# tm4cShield_eStop_v1_0.net
KiCad netlist of a schematic drawn in EAGLE
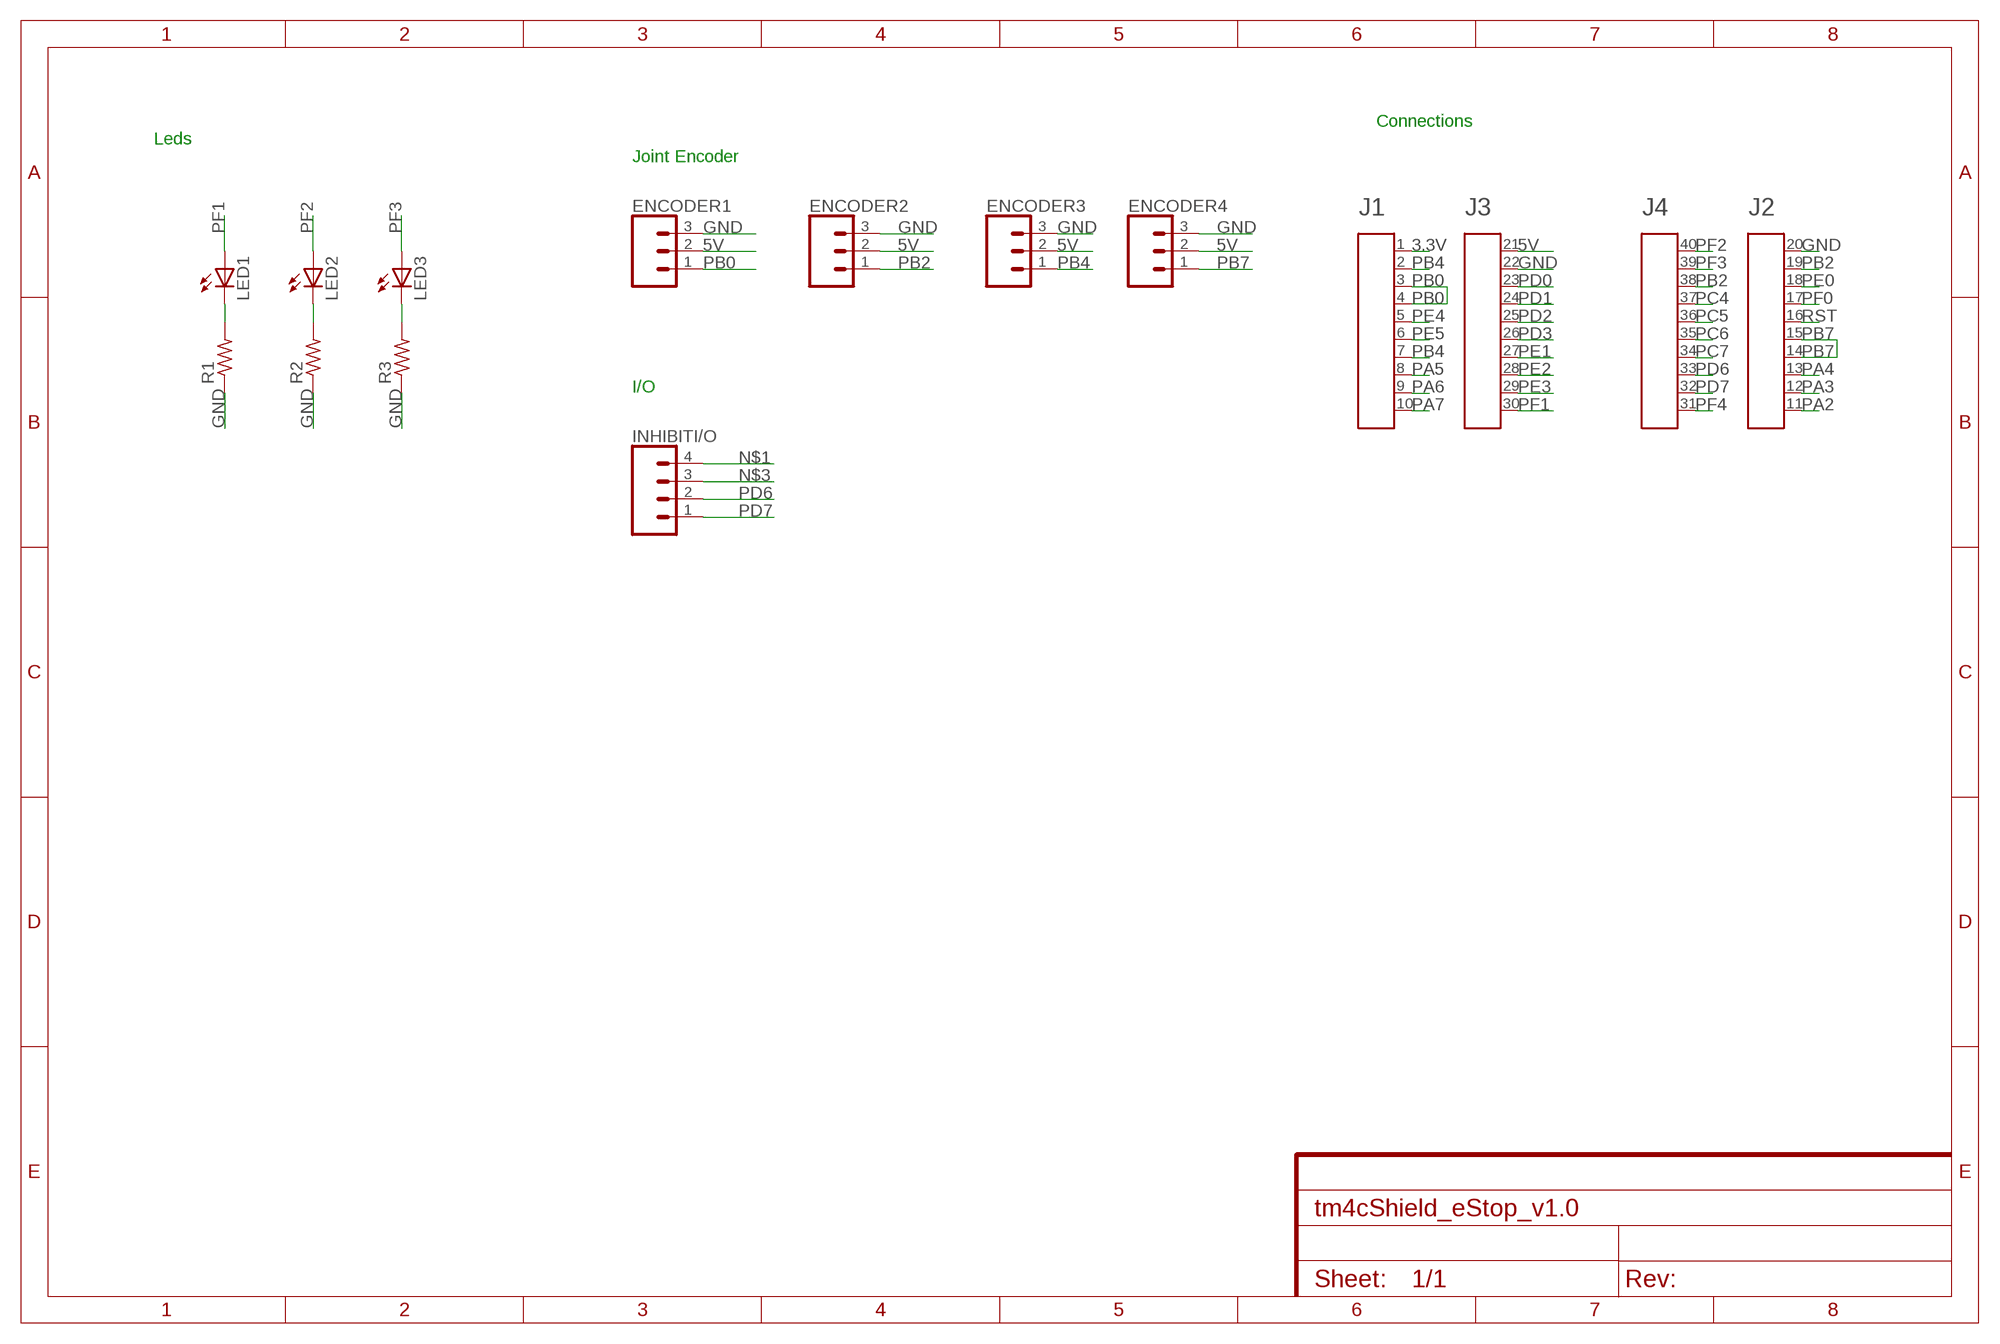
[diagram p0: schematic, sheet 1]

(export (version "E")
  (design (tool "Eeschema 10.0.6"))
  (components
    (comp (ref "A1")
      (value "HEADER4X10-BOOSTERPACK")
      (footprint "eagle-import:4X10-BOOSTERPACK")
      (libsource (lib "eagle-import") (part "HEADER4X10-BOOSTERPACK"))
    )
    (comp (ref "ENCODER1")
      (value "CONN_03JST-PTH-VERT")
      (footprint "eagle-import:JST-3-PTH-VERT")
      (libsource (lib "eagle-import") (part "CONN_03JST-PTH-VERT"))
    )
    (comp (ref "ENCODER2")
      (value "CONN_03JST-PTH-VERT")
      (footprint "eagle-import:JST-3-PTH-VERT")
      (libsource (lib "eagle-import") (part "CONN_03JST-PTH-VERT"))
    )
    (comp (ref "ENCODER3")
      (value "CONN_03JST-PTH-VERT")
      (footprint "eagle-import:JST-3-PTH-VERT")
      (libsource (lib "eagle-import") (part "CONN_03JST-PTH-VERT"))
    )
    (comp (ref "ENCODER4")
      (value "CONN_03JST-PTH-VERT")
      (footprint "eagle-import:JST-3-PTH-VERT")
      (libsource (lib "eagle-import") (part "CONN_03JST-PTH-VERT"))
    )
    (comp (ref "INHIBITI/O")
      (value "CONN_04JST-PTH-VERT")
      (footprint "eagle-import:JST-4-PTH-VERT")
      (libsource (lib "eagle-import") (part "CONN_04JST-PTH-VERT"))
    )
    (comp (ref "LED1")
      (value "LED0603")
      (footprint "eagle-import:LED-0603")
      (libsource (lib "eagle-import") (part "LED0603"))
    )
    (comp (ref "LED2")
      (value "LED0603")
      (footprint "eagle-import:LED-0603")
      (libsource (lib "eagle-import") (part "LED0603"))
    )
    (comp (ref "LED3")
      (value "LED0603")
      (footprint "eagle-import:LED-0603")
      (libsource (lib "eagle-import") (part "LED0603"))
    )
    (comp (ref "R1")
      (value "RESISTOR_0603")
      (footprint "eagle-import:RESC0603")
      (libsource (lib "eagle-import") (part "RESISTOR_0603"))
    )
    (comp (ref "R2")
      (value "RESISTOR_0603")
      (footprint "eagle-import:RESC0603")
      (libsource (lib "eagle-import") (part "RESISTOR_0603"))
    )
    (comp (ref "R3")
      (value "RESISTOR_0603")
      (footprint "eagle-import:RESC0603")
      (libsource (lib "eagle-import") (part "RESISTOR_0603"))
    )
  )
  (nets
    (net (code "1") (name "/3.3V") (class "Default")
      (node (ref "A1") (pin "1") (pinfunction "P$1_1") (pintype "bidirectional"))
    )
    (net (code "2") (name "/5V") (class "Default")
      (node (ref "A1") (pin "21") (pinfunction "P$21_21") (pintype "bidirectional"))
      (node (ref "ENCODER1") (pin "2") (pinfunction "2_2") (pintype "passive"))
      (node (ref "ENCODER2") (pin "2") (pinfunction "2_2") (pintype "passive"))
      (node (ref "ENCODER3") (pin "2") (pinfunction "2_2") (pintype "passive"))
      (node (ref "ENCODER4") (pin "2") (pinfunction "2_2") (pintype "passive"))
    )
    (net (code "3") (name "/GND") (class "Default")
      (node (ref "A1") (pin "20") (pinfunction "P$20_20") (pintype "bidirectional"))
      (node (ref "A1") (pin "22") (pinfunction "P$22_22") (pintype "bidirectional"))
      (node (ref "ENCODER1") (pin "3") (pinfunction "3_3") (pintype "passive"))
      (node (ref "ENCODER2") (pin "3") (pinfunction "3_3") (pintype "passive"))
      (node (ref "ENCODER3") (pin "3") (pinfunction "3_3") (pintype "passive"))
      (node (ref "ENCODER4") (pin "3") (pinfunction "3_3") (pintype "passive"))
      (node (ref "R1") (pin "1") (pinfunction "1_1") (pintype "passive"))
      (node (ref "R2") (pin "1") (pinfunction "1_1") (pintype "passive"))
      (node (ref "R3") (pin "1") (pinfunction "1_1") (pintype "passive"))
    )
    (net (code "4") (name "/N$1") (class "Default")
      (node (ref "INHIBITI/O") (pin "4") (pinfunction "4_4") (pintype "passive"))
    )
    (net (code "5") (name "/N$3") (class "Default")
      (node (ref "INHIBITI/O") (pin "3") (pinfunction "3_3") (pintype "passive"))
    )
    (net (code "6") (name "/PA2") (class "Default")
      (node (ref "A1") (pin "11") (pinfunction "P$11_11") (pintype "bidirectional"))
    )
    (net (code "7") (name "/PA3") (class "Default")
      (node (ref "A1") (pin "12") (pinfunction "P$12_12") (pintype "bidirectional"))
    )
    (net (code "8") (name "/PA4") (class "Default")
      (node (ref "A1") (pin "13") (pinfunction "P$13_13") (pintype "bidirectional"))
    )
    (net (code "9") (name "/PA5") (class "Default")
      (node (ref "A1") (pin "8") (pinfunction "P$8_8") (pintype "bidirectional"))
    )
    (net (code "10") (name "/PA6") (class "Default")
      (node (ref "A1") (pin "9") (pinfunction "P$9_9") (pintype "bidirectional"))
    )
    (net (code "11") (name "/PA7") (class "Default")
      (node (ref "A1") (pin "10") (pinfunction "P$10_10") (pintype "bidirectional"))
    )
    (net (code "12") (name "/PB0") (class "Default")
      (node (ref "A1") (pin "3") (pinfunction "P$3_3") (pintype "bidirectional"))
      (node (ref "A1") (pin "4") (pinfunction "P$4_4") (pintype "bidirectional"))
      (node (ref "ENCODER1") (pin "1") (pinfunction "1_1") (pintype "passive"))
    )
    (net (code "13") (name "/PB2") (class "Default")
      (node (ref "A1") (pin "19") (pinfunction "P$19_19") (pintype "bidirectional"))
      (node (ref "A1") (pin "38") (pinfunction "P$38_38") (pintype "bidirectional"))
      (node (ref "ENCODER2") (pin "1") (pinfunction "1_1") (pintype "passive"))
    )
    (net (code "14") (name "/PB4") (class "Default")
      (node (ref "A1") (pin "2") (pinfunction "P$2_2") (pintype "bidirectional"))
      (node (ref "A1") (pin "7") (pinfunction "P$7_7") (pintype "bidirectional"))
      (node (ref "ENCODER3") (pin "1") (pinfunction "1_1") (pintype "passive"))
    )
    (net (code "15") (name "/PB7") (class "Default")
      (node (ref "A1") (pin "14") (pinfunction "P$14_14") (pintype "bidirectional"))
      (node (ref "A1") (pin "15") (pinfunction "P$15_15") (pintype "bidirectional"))
      (node (ref "ENCODER4") (pin "1") (pinfunction "1_1") (pintype "passive"))
    )
    (net (code "16") (name "/PC4") (class "Default")
      (node (ref "A1") (pin "37") (pinfunction "P$37_37") (pintype "bidirectional"))
    )
    (net (code "17") (name "/PC5") (class "Default")
      (node (ref "A1") (pin "36") (pinfunction "P$36_36") (pintype "bidirectional"))
    )
    (net (code "18") (name "/PC6") (class "Default")
      (node (ref "A1") (pin "35") (pinfunction "P$35_35") (pintype "bidirectional"))
    )
    (net (code "19") (name "/PC7") (class "Default")
      (node (ref "A1") (pin "34") (pinfunction "P$34_34") (pintype "bidirectional"))
    )
    (net (code "20") (name "/PD0") (class "Default")
      (node (ref "A1") (pin "23") (pinfunction "P$23_23") (pintype "bidirectional"))
    )
    (net (code "21") (name "/PD1") (class "Default")
      (node (ref "A1") (pin "24") (pinfunction "P$24_24") (pintype "bidirectional"))
    )
    (net (code "22") (name "/PD2") (class "Default")
      (node (ref "A1") (pin "25") (pinfunction "P$25_25") (pintype "bidirectional"))
    )
    (net (code "23") (name "/PD3") (class "Default")
      (node (ref "A1") (pin "26") (pinfunction "P$26_26") (pintype "bidirectional"))
    )
    (net (code "24") (name "/PD6") (class "Default")
      (node (ref "A1") (pin "33") (pinfunction "P$33_33") (pintype "bidirectional"))
      (node (ref "INHIBITI/O") (pin "2") (pinfunction "2_2") (pintype "passive"))
    )
    (net (code "25") (name "/PD7") (class "Default")
      (node (ref "A1") (pin "32") (pinfunction "P$32_32") (pintype "bidirectional"))
      (node (ref "INHIBITI/O") (pin "1") (pinfunction "1_1") (pintype "passive"))
    )
    (net (code "26") (name "/PE0") (class "Default")
      (node (ref "A1") (pin "18") (pinfunction "P$18_18") (pintype "bidirectional"))
    )
    (net (code "27") (name "/PE1") (class "Default")
      (node (ref "A1") (pin "27") (pinfunction "P$27_27") (pintype "bidirectional"))
    )
    (net (code "28") (name "/PE2") (class "Default")
      (node (ref "A1") (pin "28") (pinfunction "P$28_28") (pintype "bidirectional"))
    )
    (net (code "29") (name "/PE3") (class "Default")
      (node (ref "A1") (pin "29") (pinfunction "P$29_29") (pintype "bidirectional"))
    )
    (net (code "30") (name "/PE4") (class "Default")
      (node (ref "A1") (pin "5") (pinfunction "P$5_5") (pintype "bidirectional"))
    )
    (net (code "31") (name "/PE5") (class "Default")
      (node (ref "A1") (pin "6") (pinfunction "P$6_6") (pintype "bidirectional"))
    )
    (net (code "32") (name "/PF0") (class "Default")
      (node (ref "A1") (pin "17") (pinfunction "P$17_17") (pintype "bidirectional"))
    )
    (net (code "33") (name "/PF1") (class "Default")
      (node (ref "A1") (pin "30") (pinfunction "P$30_30") (pintype "bidirectional"))
      (node (ref "LED1") (pin "A") (pinfunction "A_A") (pintype "passive"))
    )
    (net (code "34") (name "/PF2") (class "Default")
      (node (ref "A1") (pin "40") (pinfunction "P$40_40") (pintype "bidirectional"))
      (node (ref "LED2") (pin "A") (pinfunction "A_A") (pintype "passive"))
    )
    (net (code "35") (name "/PF3") (class "Default")
      (node (ref "A1") (pin "39") (pinfunction "P$39_39") (pintype "bidirectional"))
      (node (ref "LED3") (pin "A") (pinfunction "A_A") (pintype "passive"))
    )
    (net (code "36") (name "/PF4") (class "Default")
      (node (ref "A1") (pin "31") (pinfunction "P$31_31") (pintype "bidirectional"))
    )
    (net (code "37") (name "/RST") (class "Default")
      (node (ref "A1") (pin "16") (pinfunction "P$16_16") (pintype "bidirectional"))
    )
    (net (code "38") (name "Net-(LED1-PadC)") (class "Default")
      (node (ref "LED1") (pin "C") (pinfunction "C_C") (pintype "passive"))
      (node (ref "R1") (pin "2") (pinfunction "2_2") (pintype "passive"))
    )
    (net (code "39") (name "Net-(LED2-PadC)") (class "Default")
      (node (ref "LED2") (pin "C") (pinfunction "C_C") (pintype "passive"))
      (node (ref "R2") (pin "2") (pinfunction "2_2") (pintype "passive"))
    )
    (net (code "40") (name "Net-(LED3-PadC)") (class "Default")
      (node (ref "LED3") (pin "C") (pinfunction "C_C") (pintype "passive"))
      (node (ref "R3") (pin "2") (pinfunction "2_2") (pintype "passive"))
    )
  )
)
